# Schematics.net
KiCad netlist of a schematic drawn in EAGLE
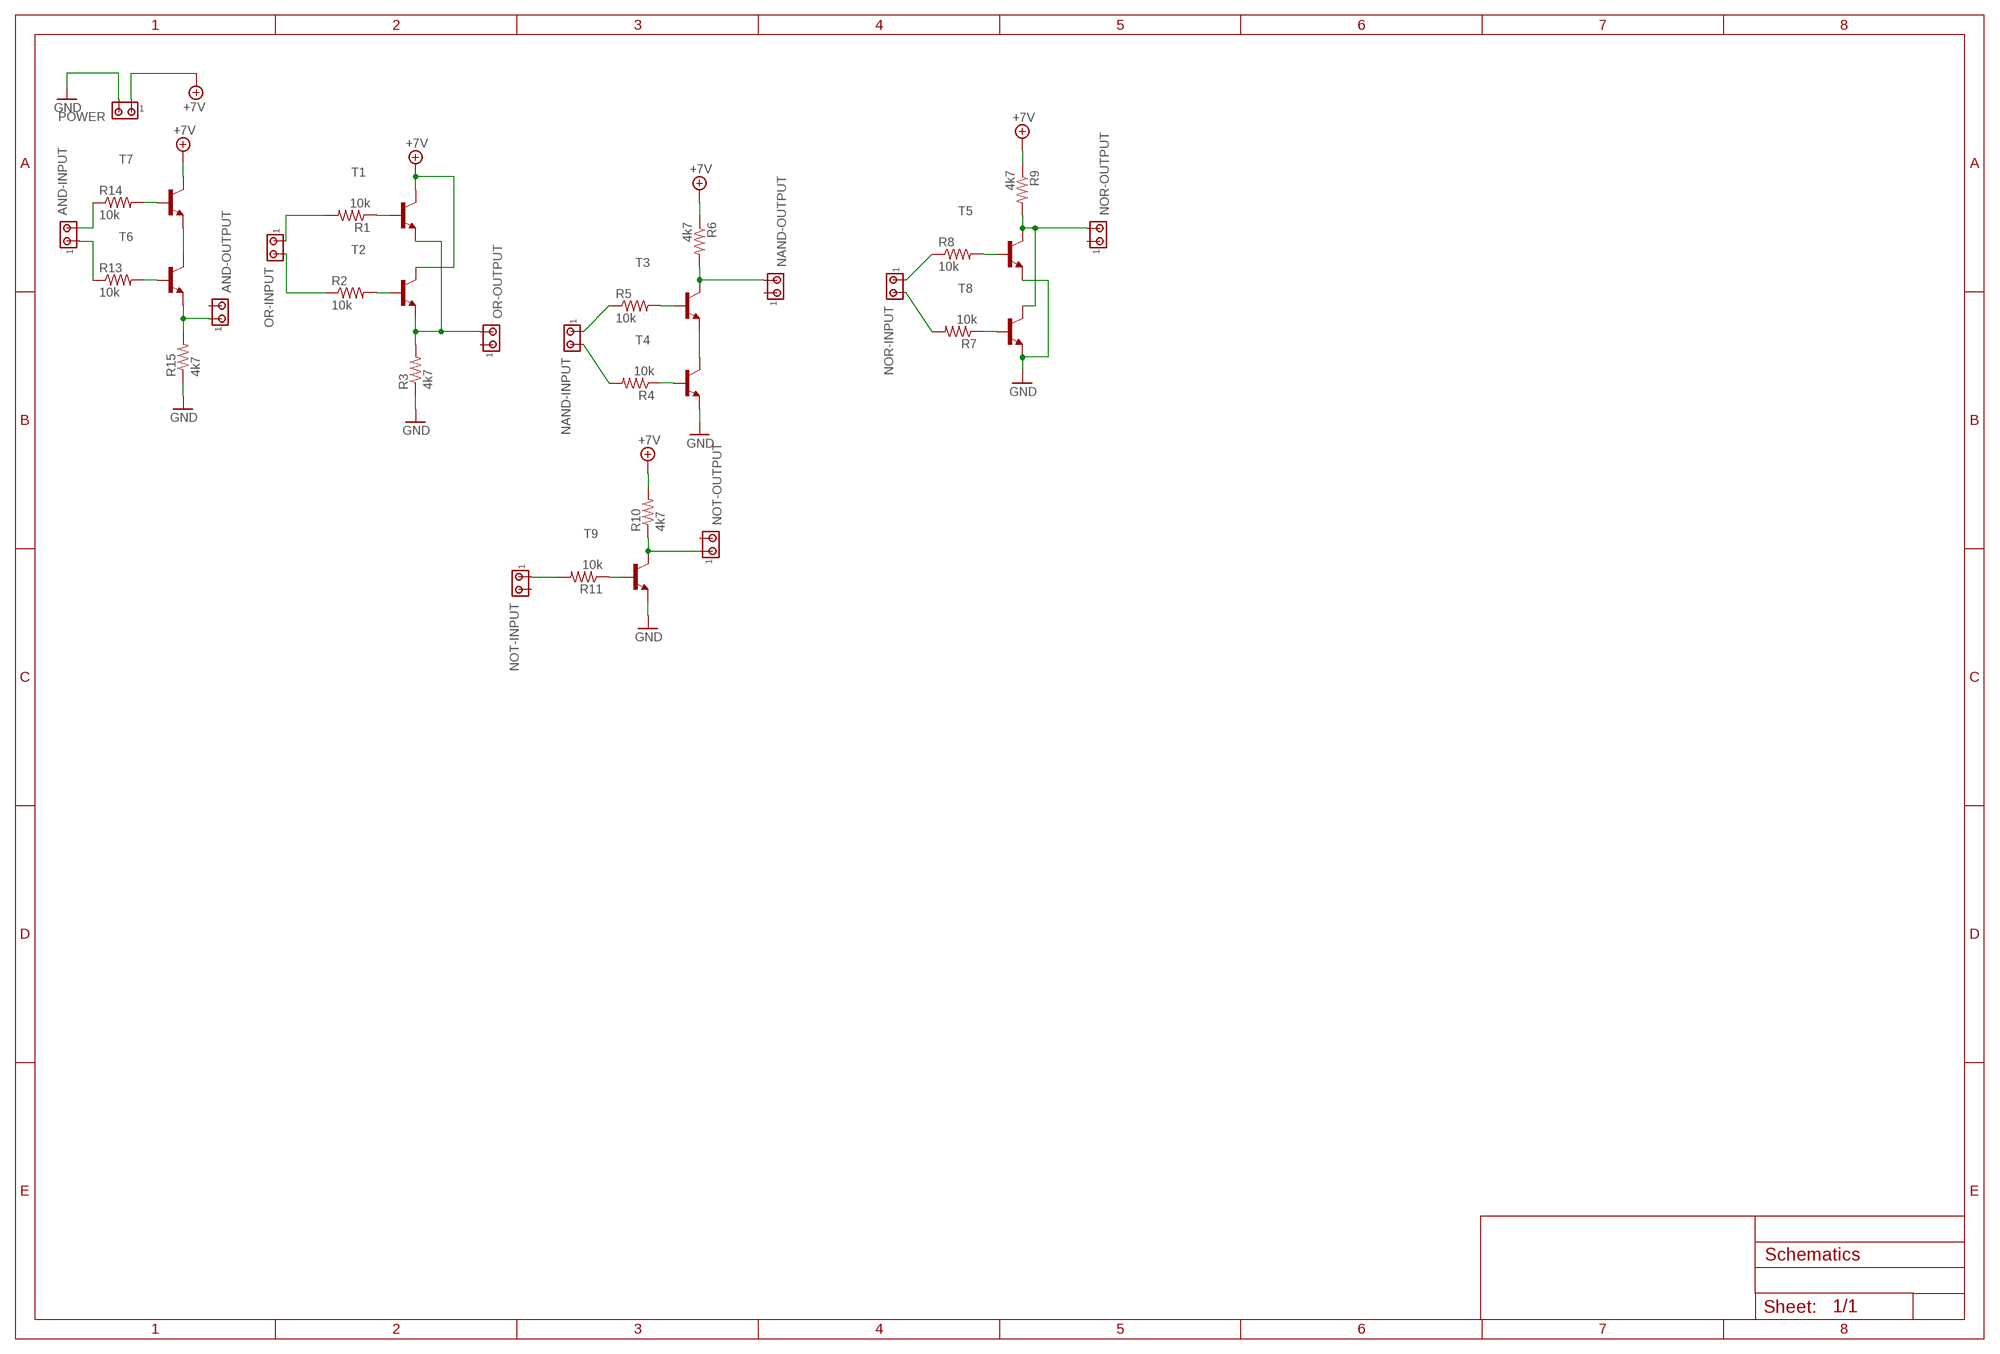
[diagram p0: schematic, sheet 1]

(export (version "E")
  (design (tool "Eeschema 10.0.6"))
  (components
    (comp (ref "AND-INPUT")
      (value "MTA02-100")
      (footprint "eagle-import:10X02MTA")
      (libsource (lib "eagle-import") (part "MTA02-100"))
    )
    (comp (ref "AND-OUTPUT")
      (value "MTA02-100")
      (footprint "eagle-import:10X02MTA")
      (libsource (lib "eagle-import") (part "MTA02-100"))
    )
    (comp (ref "NAND-INPUT")
      (value "MTA02-100")
      (footprint "eagle-import:10X02MTA")
      (libsource (lib "eagle-import") (part "MTA02-100"))
    )
    (comp (ref "NAND-OUTPUT")
      (value "MTA02-100")
      (footprint "eagle-import:10X02MTA")
      (libsource (lib "eagle-import") (part "MTA02-100"))
    )
    (comp (ref "NOR-INPUT")
      (value "MTA02-100")
      (footprint "eagle-import:10X02MTA")
      (libsource (lib "eagle-import") (part "MTA02-100"))
    )
    (comp (ref "NOR-OUTPUT")
      (value "MTA02-100")
      (footprint "eagle-import:10X02MTA")
      (libsource (lib "eagle-import") (part "MTA02-100"))
    )
    (comp (ref "NOT-INPUT")
      (value "MTA02-100")
      (footprint "eagle-import:10X02MTA")
      (libsource (lib "eagle-import") (part "MTA02-100"))
    )
    (comp (ref "NOT-OUTPUT")
      (value "MTA02-100")
      (footprint "eagle-import:10X02MTA")
      (libsource (lib "eagle-import") (part "MTA02-100"))
    )
    (comp (ref "OR-INPUT")
      (value "MTA02-100")
      (footprint "eagle-import:10X02MTA")
      (libsource (lib "eagle-import") (part "MTA02-100"))
    )
    (comp (ref "OR-OUTPUT")
      (value "MTA02-100")
      (footprint "eagle-import:10X02MTA")
      (libsource (lib "eagle-import") (part "MTA02-100"))
    )
    (comp (ref "POWER")
      (value "MTA02-100")
      (footprint "eagle-import:10X02MTA")
      (libsource (lib "eagle-import") (part "MTA02-100"))
    )
    (comp (ref "R1")
      (value "10k")
      (footprint "eagle-import:0309_12")
      (libsource (lib "eagle-import") (part "R-US_0309/12"))
    )
    (comp (ref "R2")
      (value "10k")
      (footprint "eagle-import:0309_12")
      (libsource (lib "eagle-import") (part "R-US_0309/12"))
    )
    (comp (ref "R3")
      (value "4k7")
      (footprint "eagle-import:0309_12")
      (libsource (lib "eagle-import") (part "R-US_0309/12"))
    )
    (comp (ref "R4")
      (value "10k")
      (footprint "eagle-import:0309_12")
      (libsource (lib "eagle-import") (part "R-US_0309/12"))
    )
    (comp (ref "R5")
      (value "10k")
      (footprint "eagle-import:0309_12")
      (libsource (lib "eagle-import") (part "R-US_0309/12"))
    )
    (comp (ref "R6")
      (value "4k7")
      (footprint "eagle-import:0309_12")
      (libsource (lib "eagle-import") (part "R-US_0309/12"))
    )
    (comp (ref "R7")
      (value "10k")
      (footprint "eagle-import:0309_12")
      (libsource (lib "eagle-import") (part "R-US_0309/12"))
    )
    (comp (ref "R8")
      (value "10k")
      (footprint "eagle-import:0309_12")
      (libsource (lib "eagle-import") (part "R-US_0309/12"))
    )
    (comp (ref "R9")
      (value "4k7")
      (footprint "eagle-import:0309_12")
      (libsource (lib "eagle-import") (part "R-US_0309/12"))
    )
    (comp (ref "R10")
      (value "4k7")
      (footprint "eagle-import:0309_12")
      (libsource (lib "eagle-import") (part "R-US_0309/12"))
    )
    (comp (ref "R11")
      (value "10k")
      (footprint "eagle-import:0309_12")
      (libsource (lib "eagle-import") (part "R-US_0309/12"))
    )
    (comp (ref "R13")
      (value "10k")
      (footprint "eagle-import:0309_12")
      (libsource (lib "eagle-import") (part "R-US_0309/12"))
    )
    (comp (ref "R14")
      (value "10k")
      (footprint "eagle-import:0309_12")
      (libsource (lib "eagle-import") (part "R-US_0309/12"))
    )
    (comp (ref "R15")
      (value "4k7")
      (footprint "eagle-import:0309_12")
      (libsource (lib "eagle-import") (part "R-US_0309/12"))
    )
    (comp (ref "T1")
      (value "-NPN-TO92-EBC")
      (footprint "eagle-import:TO92-EBC")
      (libsource (lib "eagle-import") (part "-NPN-TO92-EBC"))
    )
    (comp (ref "T2")
      (value "-NPN-TO92-EBC")
      (footprint "eagle-import:TO92-EBC")
      (libsource (lib "eagle-import") (part "-NPN-TO92-EBC"))
    )
    (comp (ref "T3")
      (value "-NPN-TO92-EBC")
      (footprint "eagle-import:TO92-EBC")
      (libsource (lib "eagle-import") (part "-NPN-TO92-EBC"))
    )
    (comp (ref "T4")
      (value "-NPN-TO92-EBC")
      (footprint "eagle-import:TO92-EBC")
      (libsource (lib "eagle-import") (part "-NPN-TO92-EBC"))
    )
    (comp (ref "T5")
      (value "-NPN-TO92-EBC")
      (footprint "eagle-import:TO92-EBC")
      (libsource (lib "eagle-import") (part "-NPN-TO92-EBC"))
    )
    (comp (ref "T6")
      (value "-NPN-TO92-EBC")
      (footprint "eagle-import:TO92-EBC")
      (libsource (lib "eagle-import") (part "-NPN-TO92-EBC"))
    )
    (comp (ref "T7")
      (value "-NPN-TO92-EBC")
      (footprint "eagle-import:TO92-EBC")
      (libsource (lib "eagle-import") (part "-NPN-TO92-EBC"))
    )
    (comp (ref "T8")
      (value "-NPN-TO92-EBC")
      (footprint "eagle-import:TO92-EBC")
      (libsource (lib "eagle-import") (part "-NPN-TO92-EBC"))
    )
    (comp (ref "T9")
      (value "-NPN-TO92-EBC")
      (footprint "eagle-import:TO92-EBC")
      (libsource (lib "eagle-import") (part "-NPN-TO92-EBC"))
    )
  )
  (nets
    (net (code "1") (name "+7V") (class "Default")
      (node (ref "POWER") (pin "1") (pinfunction "1_1") (pintype "passive"))
      (node (ref "R10") (pin "2") (pinfunction "2_2") (pintype "passive"))
      (node (ref "R6") (pin "1") (pinfunction "1_1") (pintype "passive"))
      (node (ref "R9") (pin "1") (pinfunction "1_1") (pintype "passive"))
      (node (ref "T1") (pin "C") (pinfunction "C_C") (pintype "passive"))
      (node (ref "T2") (pin "C") (pinfunction "C_C") (pintype "passive"))
      (node (ref "T7") (pin "C") (pinfunction "C_C") (pintype "passive"))
    )
    (net (code "2") (name "GND") (class "Default")
      (node (ref "POWER") (pin "2") (pinfunction "2_2") (pintype "passive"))
      (node (ref "R15") (pin "1") (pinfunction "1_1") (pintype "passive"))
      (node (ref "R3") (pin "1") (pinfunction "1_1") (pintype "passive"))
      (node (ref "T4") (pin "E") (pinfunction "E_E") (pintype "passive"))
      (node (ref "T5") (pin "E") (pinfunction "E_E") (pintype "passive"))
      (node (ref "T8") (pin "E") (pinfunction "E_E") (pintype "passive"))
      (node (ref "T9") (pin "E") (pinfunction "E_E") (pintype "passive"))
    )
    (net (code "3") (name "Net-(AND-INPUT-Pad1)") (class "Default")
      (node (ref "AND-INPUT") (pin "1") (pinfunction "1_1") (pintype "passive"))
      (node (ref "R13") (pin "1") (pinfunction "1_1") (pintype "passive"))
    )
    (net (code "4") (name "Net-(AND-INPUT-Pad2)") (class "Default")
      (node (ref "AND-INPUT") (pin "2") (pinfunction "2_2") (pintype "passive"))
      (node (ref "R14") (pin "1") (pinfunction "1_1") (pintype "passive"))
    )
    (net (code "5") (name "Net-(AND-OUTPUT-Pad1)") (class "Default")
      (node (ref "AND-OUTPUT") (pin "1") (pinfunction "1_1") (pintype "passive"))
      (node (ref "R15") (pin "2") (pinfunction "2_2") (pintype "passive"))
      (node (ref "T6") (pin "E") (pinfunction "E_E") (pintype "passive"))
    )
    (net (code "6") (name "Net-(NAND-INPUT-Pad1)") (class "Default")
      (node (ref "NAND-INPUT") (pin "1") (pinfunction "1_1") (pintype "passive"))
      (node (ref "R5") (pin "1") (pinfunction "1_1") (pintype "passive"))
    )
    (net (code "7") (name "Net-(NAND-INPUT-Pad2)") (class "Default")
      (node (ref "NAND-INPUT") (pin "2") (pinfunction "2_2") (pintype "passive"))
      (node (ref "R4") (pin "2") (pinfunction "2_2") (pintype "passive"))
    )
    (net (code "8") (name "Net-(NAND-OUTPUT-Pad2)") (class "Default")
      (node (ref "NAND-OUTPUT") (pin "2") (pinfunction "2_2") (pintype "passive"))
      (node (ref "R6") (pin "2") (pinfunction "2_2") (pintype "passive"))
      (node (ref "T3") (pin "C") (pinfunction "C_C") (pintype "passive"))
    )
    (net (code "9") (name "Net-(NOR-INPUT-Pad1)") (class "Default")
      (node (ref "NOR-INPUT") (pin "1") (pinfunction "1_1") (pintype "passive"))
      (node (ref "R8") (pin "1") (pinfunction "1_1") (pintype "passive"))
    )
    (net (code "10") (name "Net-(NOR-INPUT-Pad2)") (class "Default")
      (node (ref "NOR-INPUT") (pin "2") (pinfunction "2_2") (pintype "passive"))
      (node (ref "R7") (pin "2") (pinfunction "2_2") (pintype "passive"))
    )
    (net (code "11") (name "Net-(NOR-OUTPUT-Pad2)") (class "Default")
      (node (ref "NOR-OUTPUT") (pin "2") (pinfunction "2_2") (pintype "passive"))
      (node (ref "R9") (pin "2") (pinfunction "2_2") (pintype "passive"))
      (node (ref "T5") (pin "C") (pinfunction "C_C") (pintype "passive"))
      (node (ref "T8") (pin "C") (pinfunction "C_C") (pintype "passive"))
    )
    (net (code "12") (name "Net-(NOT-INPUT-Pad1)") (class "Default")
      (node (ref "NOT-INPUT") (pin "1") (pinfunction "1_1") (pintype "passive"))
      (node (ref "R11") (pin "2") (pinfunction "2_2") (pintype "passive"))
    )
    (net (code "13") (name "Net-(NOT-OUTPUT-Pad1)") (class "Default")
      (node (ref "NOT-OUTPUT") (pin "1") (pinfunction "1_1") (pintype "passive"))
      (node (ref "R10") (pin "1") (pinfunction "1_1") (pintype "passive"))
      (node (ref "T9") (pin "C") (pinfunction "C_C") (pintype "passive"))
    )
    (net (code "14") (name "Net-(OR-INPUT-Pad1)") (class "Default")
      (node (ref "OR-INPUT") (pin "1") (pinfunction "1_1") (pintype "passive"))
      (node (ref "R1") (pin "2") (pinfunction "2_2") (pintype "passive"))
    )
    (net (code "15") (name "Net-(OR-INPUT-Pad2)") (class "Default")
      (node (ref "OR-INPUT") (pin "2") (pinfunction "2_2") (pintype "passive"))
      (node (ref "R2") (pin "1") (pinfunction "1_1") (pintype "passive"))
    )
    (net (code "16") (name "Net-(OR-OUTPUT-Pad2)") (class "Default")
      (node (ref "OR-OUTPUT") (pin "2") (pinfunction "2_2") (pintype "passive"))
      (node (ref "R3") (pin "2") (pinfunction "2_2") (pintype "passive"))
      (node (ref "T1") (pin "E") (pinfunction "E_E") (pintype "passive"))
      (node (ref "T2") (pin "E") (pinfunction "E_E") (pintype "passive"))
    )
    (net (code "17") (name "Net-(R1-Pad1)") (class "Default")
      (node (ref "R1") (pin "1") (pinfunction "1_1") (pintype "passive"))
      (node (ref "T1") (pin "B") (pinfunction "B_B") (pintype "passive"))
    )
    (net (code "18") (name "Net-(R2-Pad2)") (class "Default")
      (node (ref "R2") (pin "2") (pinfunction "2_2") (pintype "passive"))
      (node (ref "T2") (pin "B") (pinfunction "B_B") (pintype "passive"))
    )
    (net (code "19") (name "Net-(R4-Pad1)") (class "Default")
      (node (ref "R4") (pin "1") (pinfunction "1_1") (pintype "passive"))
      (node (ref "T4") (pin "B") (pinfunction "B_B") (pintype "passive"))
    )
    (net (code "20") (name "Net-(R5-Pad2)") (class "Default")
      (node (ref "R5") (pin "2") (pinfunction "2_2") (pintype "passive"))
      (node (ref "T3") (pin "B") (pinfunction "B_B") (pintype "passive"))
    )
    (net (code "21") (name "Net-(R7-Pad1)") (class "Default")
      (node (ref "R7") (pin "1") (pinfunction "1_1") (pintype "passive"))
      (node (ref "T8") (pin "B") (pinfunction "B_B") (pintype "passive"))
    )
    (net (code "22") (name "Net-(R8-Pad2)") (class "Default")
      (node (ref "R8") (pin "2") (pinfunction "2_2") (pintype "passive"))
      (node (ref "T5") (pin "B") (pinfunction "B_B") (pintype "passive"))
    )
    (net (code "23") (name "Net-(R11-Pad1)") (class "Default")
      (node (ref "R11") (pin "1") (pinfunction "1_1") (pintype "passive"))
      (node (ref "T9") (pin "B") (pinfunction "B_B") (pintype "passive"))
    )
    (net (code "24") (name "Net-(R13-Pad2)") (class "Default")
      (node (ref "R13") (pin "2") (pinfunction "2_2") (pintype "passive"))
      (node (ref "T6") (pin "B") (pinfunction "B_B") (pintype "passive"))
    )
    (net (code "25") (name "Net-(R14-Pad2)") (class "Default")
      (node (ref "R14") (pin "2") (pinfunction "2_2") (pintype "passive"))
      (node (ref "T7") (pin "B") (pinfunction "B_B") (pintype "passive"))
    )
    (net (code "26") (name "Net-(T3-PadE)") (class "Default")
      (node (ref "T3") (pin "E") (pinfunction "E_E") (pintype "passive"))
      (node (ref "T4") (pin "C") (pinfunction "C_C") (pintype "passive"))
    )
    (net (code "27") (name "Net-(T6-PadC)") (class "Default")
      (node (ref "T6") (pin "C") (pinfunction "C_C") (pintype "passive"))
      (node (ref "T7") (pin "E") (pinfunction "E_E") (pintype "passive"))
    )
    (net (code "28") (name "unconnected-(AND-OUTPUT-Pad2)") (class "Default")
      (node (ref "AND-OUTPUT") (pin "2") (pinfunction "2_2") (pintype "passive"))
    )
    (net (code "29") (name "unconnected-(NAND-OUTPUT-Pad1)") (class "Default")
      (node (ref "NAND-OUTPUT") (pin "1") (pinfunction "1_1") (pintype "passive"))
    )
    (net (code "30") (name "unconnected-(NOR-OUTPUT-Pad1)") (class "Default")
      (node (ref "NOR-OUTPUT") (pin "1") (pinfunction "1_1") (pintype "passive"))
    )
    (net (code "31") (name "unconnected-(NOT-INPUT-Pad2)") (class "Default")
      (node (ref "NOT-INPUT") (pin "2") (pinfunction "2_2") (pintype "passive"))
    )
    (net (code "32") (name "unconnected-(NOT-OUTPUT-Pad2)") (class "Default")
      (node (ref "NOT-OUTPUT") (pin "2") (pinfunction "2_2") (pintype "passive"))
    )
    (net (code "33") (name "unconnected-(OR-OUTPUT-Pad1)") (class "Default")
      (node (ref "OR-OUTPUT") (pin "1") (pinfunction "1_1") (pintype "passive"))
    )
  )
)
